# Magnetometer.net
KiCad netlist of a schematic drawn in Altium Designer
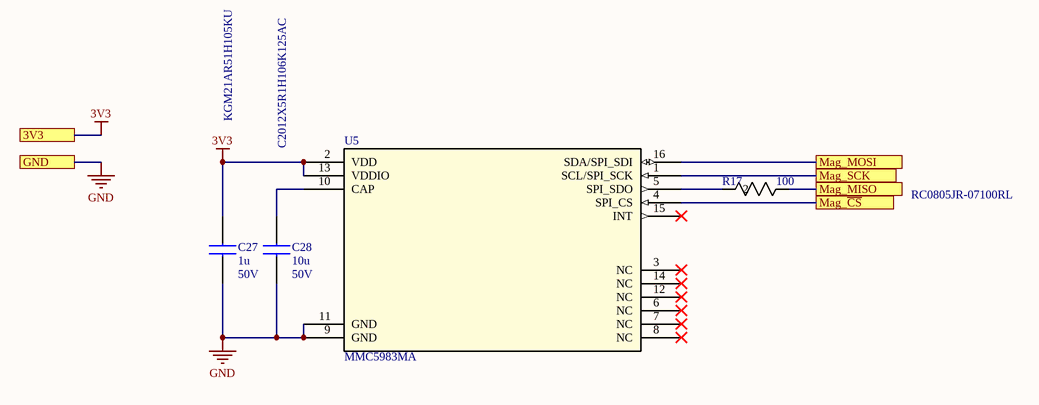
[diagram p0: Magnetometer.SchDoc]

(export (version "E")
  (design (tool "Eeschema 10.0.6"))
  (components
    (comp (ref "C27")
      (value "KGM21AR51H105KU")
      (footprint "CAPC2012X145N")
      (description "Multilayer Ceramic Chip Capacitors, Capacitance=1u")
      (fields (field (name "RATED VOLTAGE") "50V") (field (name "ALTIUM_VALUE") "1u"))
      (libsource (lib "Caps") (part "KGM21AR51H105KU"))
    )
    (comp (ref "C28")
      (value "C2012X5R1H106K125AC")
      (footprint "CAPC2012X145N")
      (description "Multilayer Ceramic Chip Capacitors, Capacitance=10?F, LxWxT:2x1.25x1.25mm")
      (fields
        (field (name "MOUSER PART NUMBER") "810-C2012X5R1H106K12")
        (field (name "RATED VOLTAGE") "50V")
        (field (name "ALTIUM_VALUE") "10u")
      )
      (libsource (lib "Caps") (part "C2012X5R1H106K125AC"))
    )
    (comp (ref "R17")
      (value "RC0805JR-07100RL")
      (footprint "RC0805N_YAG")
      (description "RES 0805 100 5% 1/8W")
      (fields (field (name "TOLERANCE") "5%") (field (name "ALTIUM_VALUE") "100"))
      (libsource (lib "Resistors") (part "RC0805JR-07100RL"))
    )
    (comp (ref "U5")
      (value "MMC5983MA")
      (footprint "MMC5983MA_MEM")
      (description "No Description Available")
      (fields (field (name "COPYRIGHT") "Copyright (C) 2025 Ultra Librarian. All rights reserved."))
      (libsource (lib "MMC5983MA") (part "MMC5983MA"))
    )
  )
  (nets
    (net (code "1") (name "/Mag_MISO") (class "Default")
      (node (ref "R17") (pin "1") (pinfunction "1_1") (pintype "passive"))
    )
    (net (code "2") (name "/Mag_MOSI") (class "Default")
      (node (ref "U5") (pin "16") (pinfunction "SDA/SPI_SDI_16") (pintype "bidirectional"))
    )
    (net (code "3") (name "/Mag_SCK") (class "Default")
      (node (ref "U5") (pin "1") (pinfunction "SCL/SPI_SCK_1") (pintype "input"))
    )
    (net (code "4") (name "/Mag_~{CS}") (class "Default")
      (node (ref "U5") (pin "4") (pinfunction "SPI_CS_4") (pintype "input"))
    )
    (net (code "5") (name "3V3") (class "Default")
      (node (ref "C27") (pin "2") (pinfunction "2_2") (pintype "passive"))
      (node (ref "U5") (pin "13") (pinfunction "VDDIO_13") (pintype "power_in"))
      (node (ref "U5") (pin "2") (pinfunction "VDD_2") (pintype "power_in"))
    )
    (net (code "6") (name "GND") (class "Default")
      (node (ref "C27") (pin "1") (pinfunction "1_1") (pintype "passive"))
      (node (ref "C28") (pin "1") (pinfunction "1_1") (pintype "passive"))
      (node (ref "U5") (pin "11") (pinfunction "GND_11") (pintype "power_in"))
      (node (ref "U5") (pin "9") (pinfunction "GND_9") (pintype "power_in"))
    )
    (net (code "7") (name "Net-(U5-CAP)") (class "Default")
      (node (ref "C28") (pin "2") (pinfunction "2_2") (pintype "passive"))
      (node (ref "U5") (pin "10") (pinfunction "CAP_10") (pintype "power_in"))
    )
    (net (code "8") (name "Net-(U5-SPI_SDO)") (class "Default")
      (node (ref "R17") (pin "2") (pinfunction "2_2") (pintype "passive"))
      (node (ref "U5") (pin "5") (pinfunction "SPI_SDO_5") (pintype "output"))
    )
    (net (code "9") (name "unconnected-(U5-INT-Pad15)") (class "Default")
      (node (ref "U5") (pin "15") (pinfunction "INT_15") (pintype "output+no_connect"))
    )
    (net (code "10") (name "unconnected-(U5-NC-Pad3)") (class "Default")
      (node (ref "U5") (pin "3") (pinfunction "NC_3") (pintype "passive+no_connect"))
    )
    (net (code "11") (name "unconnected-(U5-NC-Pad6)") (class "Default")
      (node (ref "U5") (pin "6") (pinfunction "NC_6") (pintype "passive+no_connect"))
    )
    (net (code "12") (name "unconnected-(U5-NC-Pad7)") (class "Default")
      (node (ref "U5") (pin "7") (pinfunction "NC_7") (pintype "passive+no_connect"))
    )
    (net (code "13") (name "unconnected-(U5-NC-Pad8)") (class "Default")
      (node (ref "U5") (pin "8") (pinfunction "NC_8") (pintype "passive+no_connect"))
    )
    (net (code "14") (name "unconnected-(U5-NC-Pad12)") (class "Default")
      (node (ref "U5") (pin "12") (pinfunction "NC_12") (pintype "passive+no_connect"))
    )
    (net (code "15") (name "unconnected-(U5-NC-Pad14)") (class "Default")
      (node (ref "U5") (pin "14") (pinfunction "NC_14") (pintype "passive+no_connect"))
    )
  )
)
